# KELU1-0234.net
KiCad netlist of a schematic drawn in EAGLE
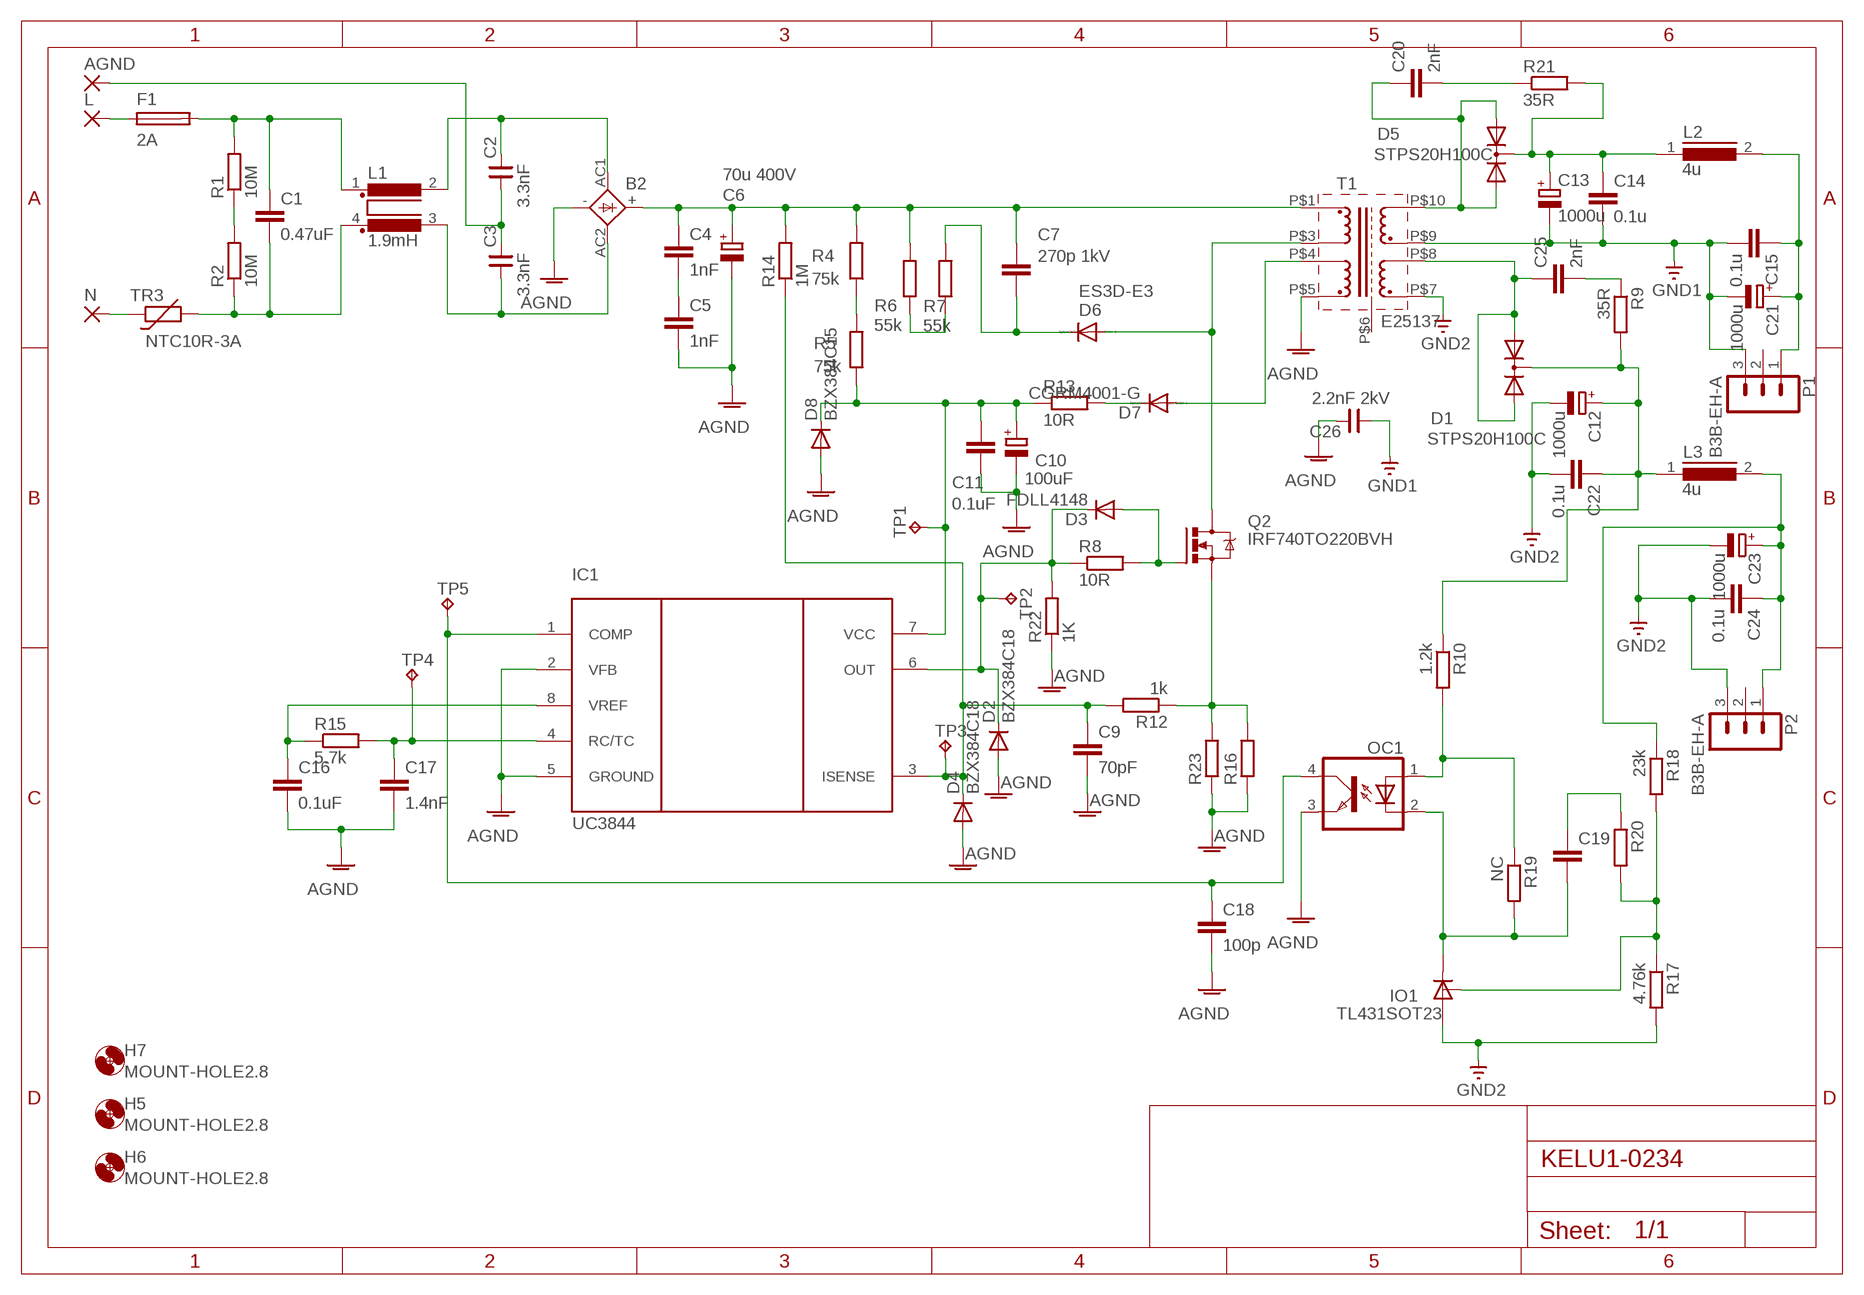
[diagram p0: schematic, sheet 1]

(export (version "E")
  (design (tool "Eeschema 10.0.6"))
  (components
    (comp (ref "AGND")
      (value "3,17/1,1")
      (footprint "eagle-import:3,17_1,1")
      (libsource (lib "eagle-import") (part "3,17/1,1"))
    )
    (comp (ref "B2")
      (value "2KBP")
      (footprint "eagle-import:2KBP")
      (libsource (lib "eagle-import") (part "2KBP"))
    )
    (comp (ref "C1")
      (value "0.47uF")
      (footprint "eagle-import:C15B5")
      (libsource (lib "eagle-import") (part "C15/5"))
    )
    (comp (ref "C2")
      (value "3.3nF")
      (footprint "eagle-import:C085-110X050")
      (libsource (lib "eagle-import") (part "CNP-C085-110X050"))
    )
    (comp (ref "C3")
      (value "3.3nF")
      (footprint "eagle-import:C080-110X045")
      (libsource (lib "eagle-import") (part "CNP-C080-110X045"))
    )
    (comp (ref "C4")
      (value "1nF")
      (footprint "eagle-import:C1206K")
      (libsource (lib "eagle-import") (part "C-EUC1206K"))
    )
    (comp (ref "C5")
      (value "1nF")
      (footprint "eagle-import:C1206K")
      (libsource (lib "eagle-import") (part "C-EUC1206K"))
    )
    (comp (ref "C6")
      (value "70u 400V")
      (footprint "eagle-import:E7,5-16")
      (libsource (lib "eagle-import") (part "CPOL-EUE7.5-16"))
    )
    (comp (ref "C7")
      (value "270p 1kV")
      (footprint "eagle-import:C1206K")
      (libsource (lib "eagle-import") (part "C-EUC1206K"))
    )
    (comp (ref "C9")
      (value "70pF")
      (footprint "eagle-import:C0805K")
      (libsource (lib "eagle-import") (part "resistor_C-EUC0805K"))
    )
    (comp (ref "C10")
      (value "100uF")
      (footprint "eagle-import:E5-5")
      (libsource (lib "eagle-import") (part "resistor_CPOL-EUE5-5"))
    )
    (comp (ref "C11")
      (value "0.1uF")
      (footprint "eagle-import:C0805K")
      (libsource (lib "eagle-import") (part "resistor_C-EUC0805K"))
    )
    (comp (ref "C12")
      (value "1000u")
      (footprint "eagle-import:E3,5-8")
      (libsource (lib "eagle-import") (part "resistor_CPOL-EUE3.5-8"))
    )
    (comp (ref "C13")
      (value "1000u")
      (footprint "eagle-import:E3,5-8")
      (libsource (lib "eagle-import") (part "resistor_CPOL-EUE3.5-8"))
    )
    (comp (ref "C14")
      (value "0.1u")
      (footprint "eagle-import:C0805K")
      (libsource (lib "eagle-import") (part "resistor_C-EUC0805K"))
    )
    (comp (ref "C15")
      (value "0.1u")
      (footprint "eagle-import:C0805K")
      (libsource (lib "eagle-import") (part "resistor_C-EUC0805K"))
    )
    (comp (ref "C16")
      (value "0.1uF")
      (footprint "eagle-import:C0805K")
      (libsource (lib "eagle-import") (part "resistor_C-EUC0805K"))
    )
    (comp (ref "C17")
      (value "1.4nF")
      (footprint "eagle-import:C0805K")
      (libsource (lib "eagle-import") (part "resistor_C-EUC0805K"))
    )
    (comp (ref "C18")
      (value "100p")
      (footprint "eagle-import:C0805K")
      (libsource (lib "eagle-import") (part "resistor_C-EUC0805K"))
    )
    (comp (ref "C19")
      (value "C-EUC0805K")
      (footprint "eagle-import:C0805K")
      (libsource (lib "eagle-import") (part "resistor_C-EUC0805K"))
    )
    (comp (ref "C20")
      (value "2nF")
      (footprint "eagle-import:C1206K")
      (libsource (lib "eagle-import") (part "C-EUC1206K"))
    )
    (comp (ref "C21")
      (value "1000u")
      (footprint "eagle-import:E3,5-8")
      (libsource (lib "eagle-import") (part "resistor_CPOL-EUE3.5-8"))
    )
    (comp (ref "C22")
      (value "0.1u")
      (footprint "eagle-import:C0805K")
      (libsource (lib "eagle-import") (part "resistor_C-EUC0805K"))
    )
    (comp (ref "C23")
      (value "1000u")
      (footprint "eagle-import:E3,5-8")
      (libsource (lib "eagle-import") (part "resistor_CPOL-EUE3.5-8"))
    )
    (comp (ref "C24")
      (value "0.1u")
      (footprint "eagle-import:C0805K")
      (libsource (lib "eagle-import") (part "resistor_C-EUC0805K"))
    )
    (comp (ref "C25")
      (value "2nF")
      (footprint "eagle-import:C1206K")
      (libsource (lib "eagle-import") (part "C-EUC1206K"))
    )
    (comp (ref "C26")
      (value "2.2nF 2kV")
      (footprint "eagle-import:C080-110X045")
      (libsource (lib "eagle-import") (part "CNP-C080-110X045"))
    )
    (comp (ref "D1")
      (value "STPS20H100C")
      (footprint "eagle-import:TO220ABS")
      (libsource (lib "eagle-import") (part "BYV32"))
    )
    (comp (ref "D2")
      (value "BZX384C18")
      (footprint "eagle-import:SOD323-W")
      (libsource (lib "eagle-import") (part "diode-1_DIODE-SOD323-W"))
    )
    (comp (ref "D3")
      (value "FDLL4148")
      (footprint "eagle-import:MINIMELF")
      (libsource (lib "eagle-import") (part "diode-1_DIODE-MINIMELF"))
    )
    (comp (ref "D4")
      (value "BZX384C18")
      (footprint "eagle-import:SOD323-W")
      (libsource (lib "eagle-import") (part "diode-1_DIODE-SOD323-W"))
    )
    (comp (ref "D5")
      (value "STPS20H100C")
      (footprint "eagle-import:TO220ABS")
      (libsource (lib "eagle-import") (part "BYV32"))
    )
    (comp (ref "D6")
      (value "ES3D-E3")
      (footprint "eagle-import:SMC")
      (libsource (lib "eagle-import") (part "DIODE-SMC"))
    )
    (comp (ref "D7")
      (value "CGRM4001-G")
      (footprint "eagle-import:SOD-123_MINI-SMA")
      (libsource (lib "eagle-import") (part "CGRM400-G1"))
    )
    (comp (ref "D8")
      (value "BZX384C15")
      (footprint "eagle-import:SOD323-W")
      (libsource (lib "eagle-import") (part "diode-1_DIODE-SOD323-W"))
    )
    (comp (ref "F1")
      (value "2A")
      (footprint "eagle-import:TE5")
      (libsource (lib "eagle-import") (part "FUSETE5"))
    )
    (comp (ref "H5")
      (value "MOUNT-HOLE2.8")
      (footprint "eagle-import:2,8")
      (libsource (lib "eagle-import") (part "MOUNT-HOLE2.8"))
    )
    (comp (ref "H6")
      (value "MOUNT-HOLE2.8")
      (footprint "eagle-import:2,8")
      (libsource (lib "eagle-import") (part "MOUNT-HOLE2.8"))
    )
    (comp (ref "H7")
      (value "MOUNT-HOLE2.8")
      (footprint "eagle-import:2,8")
      (libsource (lib "eagle-import") (part "MOUNT-HOLE2.8"))
    )
    (comp (ref "IC1")
      (value "UC3844")
      (footprint "eagle-import:SOIC08")
      (libsource (lib "eagle-import") (part "UC3844"))
    )
    (comp (ref "IO1")
      (value "TL431SOT23")
      (footprint "eagle-import:SOT23")
      (fields (field (name "MPN") "TL431BFDT"))
      (libsource (lib "eagle-import") (part "TL431SOT23"))
    )
    (comp (ref "L")
      (value "3,17/1,1")
      (footprint "eagle-import:3,17_1,1")
      (libsource (lib "eagle-import") (part "3,17/1,1"))
    )
    (comp (ref "L1")
      (value "1.9mH")
      (footprint "eagle-import:MFE")
      (libsource (lib "eagle-import") (part "MFE"))
    )
    (comp (ref "L2")
      (value "4u")
      (footprint "eagle-import:82114R")
      (libsource (lib "eagle-import") (part "82114R"))
    )
    (comp (ref "L3")
      (value "4u")
      (footprint "eagle-import:82114R")
      (libsource (lib "eagle-import") (part "82114R"))
    )
    (comp (ref "N")
      (value "3,17/1,1")
      (footprint "eagle-import:3,17_1,1")
      (libsource (lib "eagle-import") (part "3,17/1,1"))
    )
    (comp (ref "OC1")
      (value "PC817")
      (footprint "eagle-import:DIL04")
      (libsource (lib "eagle-import") (part "PC817"))
    )
    (comp (ref "P1")
      (value "B3B-EH-A")
      (footprint "eagle-import:B3B-EH-A")
      (libsource (lib "eagle-import") (part "B3B-EH-A"))
    )
    (comp (ref "P2")
      (value "B3B-EH-A")
      (footprint "eagle-import:B3B-EH-A")
      (libsource (lib "eagle-import") (part "B3B-EH-A"))
    )
    (comp (ref "Q2")
      (value "IRF740TO220BVH")
      (footprint "eagle-import:TO220BVH")
      (libsource (lib "eagle-import") (part "IRF740TO220BVH"))
    )
    (comp (ref "R1")
      (value "10M")
      (footprint "eagle-import:M1206")
      (libsource (lib "eagle-import") (part "R-EU_M1206"))
    )
    (comp (ref "R2")
      (value "10M")
      (footprint "eagle-import:M1206")
      (libsource (lib "eagle-import") (part "R-EU_M1206"))
    )
    (comp (ref "R4")
      (value "75k")
      (footprint "eagle-import:M1206")
      (libsource (lib "eagle-import") (part "R-EU_M1206"))
    )
    (comp (ref "R5")
      (value "75k")
      (footprint "eagle-import:M1206")
      (libsource (lib "eagle-import") (part "R-EU_M1206"))
    )
    (comp (ref "R6")
      (value "55k")
      (footprint "eagle-import:M1206")
      (libsource (lib "eagle-import") (part "R-EU_M1206"))
    )
    (comp (ref "R7")
      (value "55k")
      (footprint "eagle-import:M1206")
      (libsource (lib "eagle-import") (part "R-EU_M1206"))
    )
    (comp (ref "R8")
      (value "10R")
      (footprint "eagle-import:M1206")
      (libsource (lib "eagle-import") (part "resistor_R-EU_M1206"))
    )
    (comp (ref "R9")
      (value "35R")
      (footprint "eagle-import:M1206")
      (libsource (lib "eagle-import") (part "R-EU_M1206"))
    )
    (comp (ref "R10")
      (value "1.2k")
      (footprint "eagle-import:R0805W")
      (libsource (lib "eagle-import") (part "resistor_R-EU_R0805W"))
    )
    (comp (ref "R12")
      (value "1k")
      (footprint "eagle-import:R0805W")
      (libsource (lib "eagle-import") (part "resistor_R-EU_R0805W"))
    )
    (comp (ref "R13")
      (value "10R")
      (footprint "eagle-import:R0805W")
      (libsource (lib "eagle-import") (part "resistor_R-EU_R0805W"))
    )
    (comp (ref "R14")
      (value "1M")
      (footprint "eagle-import:M1206")
      (libsource (lib "eagle-import") (part "R-EU_M1206"))
    )
    (comp (ref "R15")
      (value "5.7k")
      (footprint "eagle-import:R0805W")
      (libsource (lib "eagle-import") (part "resistor_R-EU_R0805W"))
    )
    (comp (ref "R16")
      (value "R-EU_R2512")
      (footprint "eagle-import:R2512")
      (libsource (lib "eagle-import") (part "R-EU_R2512"))
    )
    (comp (ref "R17")
      (value "4.76k")
      (footprint "eagle-import:R0805W")
      (libsource (lib "eagle-import") (part "resistor_R-EU_R0805W"))
    )
    (comp (ref "R18")
      (value "23k")
      (footprint "eagle-import:R0805W")
      (libsource (lib "eagle-import") (part "resistor_R-EU_R0805W"))
    )
    (comp (ref "R19")
      (value "NC")
      (footprint "eagle-import:R0805W")
      (libsource (lib "eagle-import") (part "resistor_R-EU_R0805W"))
    )
    (comp (ref "R20")
      (value "R-EU_R0805W")
      (footprint "eagle-import:R0805W")
      (libsource (lib "eagle-import") (part "resistor_R-EU_R0805W"))
    )
    (comp (ref "R21")
      (value "35R")
      (footprint "eagle-import:M1206")
      (libsource (lib "eagle-import") (part "R-EU_M1206"))
    )
    (comp (ref "R22")
      (value "1K")
      (footprint "eagle-import:M1206")
      (libsource (lib "eagle-import") (part "resistor_R-EU_M1206"))
    )
    (comp (ref "R23")
      (value "R-EU_R2512")
      (footprint "eagle-import:R2512")
      (libsource (lib "eagle-import") (part "R-EU_R2512"))
    )
    (comp (ref "T1")
      (value "E25137")
      (footprint "eagle-import:E25137")
      (libsource (lib "eagle-import") (part "E25137"))
    )
    (comp (ref "TP1")
      (value "TPB1,27")
      (footprint "eagle-import:B1,27")
      (libsource (lib "eagle-import") (part "TPB1,27"))
    )
    (comp (ref "TP2")
      (value "TPB1,27")
      (footprint "eagle-import:B1,27")
      (libsource (lib "eagle-import") (part "TPB1,27"))
    )
    (comp (ref "TP3")
      (value "TPB1,27")
      (footprint "eagle-import:B1,27")
      (libsource (lib "eagle-import") (part "TPB1,27"))
    )
    (comp (ref "TP4")
      (value "TPB1,27")
      (footprint "eagle-import:B1,27")
      (libsource (lib "eagle-import") (part "TPB1,27"))
    )
    (comp (ref "TP5")
      (value "TPB1,27")
      (footprint "eagle-import:B1,27")
      (libsource (lib "eagle-import") (part "TPB1,27"))
    )
    (comp (ref "TR3")
      (value "NTC10R-3A")
      (footprint "eagle-import:R-5")
      (libsource (lib "eagle-import") (part "THERMISTOR-5"))
    )
  )
  (nets
    (net (code "1") (name "AGND") (class "Default")
      (node (ref "B2") (pin "-") (pinfunction "-_-") (pintype "passive"))
      (node (ref "C10") (pin "-") (pinfunction "-_-") (pintype "passive"))
      (node (ref "C11") (pin "2") (pinfunction "2_2") (pintype "passive"))
      (node (ref "C16") (pin "2") (pinfunction "2_2") (pintype "passive"))
      (node (ref "C17") (pin "2") (pinfunction "2_2") (pintype "passive"))
      (node (ref "C18") (pin "2") (pinfunction "2_2") (pintype "passive"))
      (node (ref "C26") (pin "2") (pinfunction "2_2") (pintype "passive"))
      (node (ref "C5") (pin "2") (pinfunction "2_2") (pintype "passive"))
      (node (ref "C6") (pin "-") (pinfunction "-_-") (pintype "passive"))
      (node (ref "C9") (pin "2") (pinfunction "2_2") (pintype "passive"))
      (node (ref "D2") (pin "A") (pinfunction "A_A") (pintype "passive"))
      (node (ref "D4") (pin "A") (pinfunction "A_A") (pintype "passive"))
      (node (ref "D8") (pin "A") (pinfunction "A_A") (pintype "passive"))
      (node (ref "IC1") (pin "2") (pinfunction "VFB_2") (pintype "bidirectional"))
      (node (ref "IC1") (pin "5") (pinfunction "GROUND_5") (pintype "bidirectional"))
      (node (ref "OC1") (pin "3") (pinfunction "EMIT_3") (pintype "passive"))
      (node (ref "R16") (pin "1") (pinfunction "1_1") (pintype "passive"))
      (node (ref "R22") (pin "1") (pinfunction "1_1") (pintype "passive"))
      (node (ref "R23") (pin "1") (pinfunction "1_1") (pintype "passive"))
      (node (ref "T1") (pin "P$5") (pinfunction "5_P$5") (pintype "passive"))
    )
    (net (code "2") (name "GND1") (class "Default")
      (node (ref "C13") (pin "-") (pinfunction "-_-") (pintype "passive"))
      (node (ref "C14") (pin "2") (pinfunction "2_2") (pintype "passive"))
      (node (ref "C15") (pin "2") (pinfunction "2_2") (pintype "passive"))
      (node (ref "C21") (pin "-") (pinfunction "-_-") (pintype "passive"))
      (node (ref "C26") (pin "1") (pinfunction "1_1") (pintype "passive"))
      (node (ref "P1") (pin "3") (pinfunction "3_3") (pintype "passive"))
      (node (ref "T1") (pin "P$9") (pinfunction "9_P$9") (pintype "passive"))
    )
    (net (code "3") (name "GND2") (class "Default")
      (node (ref "C12") (pin "-") (pinfunction "-_-") (pintype "passive"))
      (node (ref "C22") (pin "2") (pinfunction "2_2") (pintype "passive"))
      (node (ref "C23") (pin "-") (pinfunction "-_-") (pintype "passive"))
      (node (ref "C24") (pin "2") (pinfunction "2_2") (pintype "passive"))
      (node (ref "IO1") (pin "3") (pinfunction "A_3") (pintype "bidirectional"))
      (node (ref "P2") (pin "3") (pinfunction "3_3") (pintype "passive"))
      (node (ref "R17") (pin "2") (pinfunction "2_2") (pintype "passive"))
      (node (ref "T1") (pin "P$7") (pinfunction "7_P$7") (pintype "passive"))
    )
    (net (code "4") (name "Net-(AGND-P)") (class "Default")
      (node (ref "AGND") (pin "1") (pinfunction "P_1") (pintype "passive"))
      (node (ref "C2") (pin "1") (pinfunction "1_1") (pintype "passive"))
      (node (ref "C3") (pin "2") (pinfunction "2_2") (pintype "passive"))
    )
    (net (code "5") (name "Net-(B2-PadAC1)") (class "Default")
      (node (ref "B2") (pin "AC1") (pinfunction "AC1_AC1") (pintype "passive"))
      (node (ref "C2") (pin "2") (pinfunction "2_2") (pintype "passive"))
      (node (ref "L1") (pin "2") (pinfunction "2_2") (pintype "passive"))
    )
    (net (code "6") (name "Net-(C1-Pad1)") (class "Default")
      (node (ref "C1") (pin "1") (pinfunction "1_1") (pintype "passive"))
      (node (ref "F1") (pin "2") (pinfunction "2_2") (pintype "passive"))
      (node (ref "L1") (pin "1") (pinfunction "1_1") (pintype "passive"))
      (node (ref "R1") (pin "2") (pinfunction "2_2") (pintype "passive"))
    )
    (net (code "7") (name "Net-(C4-Pad2)") (class "Default")
      (node (ref "C4") (pin "2") (pinfunction "2_2") (pintype "passive"))
      (node (ref "C5") (pin "1") (pinfunction "1_1") (pintype "passive"))
    )
    (net (code "8") (name "Net-(C7-Pad2)") (class "Default")
      (node (ref "C7") (pin "2") (pinfunction "2_2") (pintype "passive"))
      (node (ref "D6") (pin "C") (pinfunction "C_C") (pintype "passive"))
      (node (ref "R7") (pin "2") (pinfunction "2_2") (pintype "passive"))
    )
    (net (code "9") (name "Net-(C12-Pad+)") (class "Default")
      (node (ref "C12") (pin "+") (pinfunction "+_+") (pintype "passive"))
      (node (ref "C22") (pin "1") (pinfunction "1_1") (pintype "passive"))
      (node (ref "D1") (pin "C") (pinfunction "C_C") (pintype "passive"))
      (node (ref "L3") (pin "1") (pinfunction "1_1") (pintype "passive"))
      (node (ref "R10") (pin "1") (pinfunction "1_1") (pintype "passive"))
      (node (ref "R9") (pin "2") (pinfunction "2_2") (pintype "passive"))
    )
    (net (code "10") (name "Net-(C13-Pad+)") (class "Default")
      (node (ref "C13") (pin "+") (pinfunction "+_+") (pintype "passive"))
      (node (ref "C14") (pin "1") (pinfunction "1_1") (pintype "passive"))
      (node (ref "D5") (pin "C") (pinfunction "C_C") (pintype "passive"))
      (node (ref "L2") (pin "1") (pinfunction "1_1") (pintype "passive"))
      (node (ref "R21") (pin "2") (pinfunction "2_2") (pintype "passive"))
    )
    (net (code "11") (name "Net-(C15-Pad1)") (class "Default")
      (node (ref "C15") (pin "1") (pinfunction "1_1") (pintype "passive"))
      (node (ref "C21") (pin "+") (pinfunction "+_+") (pintype "passive"))
      (node (ref "L2") (pin "2") (pinfunction "2_2") (pintype "passive"))
      (node (ref "P1") (pin "1") (pinfunction "1_1") (pintype "passive"))
    )
    (net (code "12") (name "Net-(C19-Pad1)") (class "Default")
      (node (ref "C19") (pin "1") (pinfunction "1_1") (pintype "passive"))
      (node (ref "R20") (pin "1") (pinfunction "1_1") (pintype "passive"))
    )
    (net (code "13") (name "Net-(C20-Pad2)") (class "Default")
      (node (ref "C20") (pin "2") (pinfunction "2_2") (pintype "passive"))
      (node (ref "R21") (pin "1") (pinfunction "1_1") (pintype "passive"))
    )
    (net (code "14") (name "Net-(C23-Pad+)") (class "Default")
      (node (ref "C23") (pin "+") (pinfunction "+_+") (pintype "passive"))
      (node (ref "C24") (pin "1") (pinfunction "1_1") (pintype "passive"))
      (node (ref "L3") (pin "2") (pinfunction "2_2") (pintype "passive"))
      (node (ref "P2") (pin "1") (pinfunction "1_1") (pintype "passive"))
      (node (ref "R18") (pin "1") (pinfunction "1_1") (pintype "passive"))
    )
    (net (code "15") (name "Net-(C25-Pad2)") (class "Default")
      (node (ref "C25") (pin "2") (pinfunction "2_2") (pintype "passive"))
      (node (ref "R9") (pin "1") (pinfunction "1_1") (pintype "passive"))
    )
    (net (code "16") (name "Net-(D3-PadA)") (class "Default")
      (node (ref "D3") (pin "A") (pinfunction "A_A") (pintype "passive"))
      (node (ref "Q2") (pin "G") (pinfunction "G_G") (pintype "passive"))
      (node (ref "R8") (pin "2") (pinfunction "2_2") (pintype "passive"))
    )
    (net (code "17") (name "Net-(D7-PadC)") (class "Default")
      (node (ref "D7") (pin "C") (pinfunction "C_C") (pintype "passive"))
      (node (ref "R13") (pin "2") (pinfunction "2_2") (pintype "passive"))
    )
    (net (code "18") (name "Net-(IC1-COMP)") (class "Default")
      (node (ref "C18") (pin "1") (pinfunction "1_1") (pintype "passive"))
      (node (ref "IC1") (pin "1") (pinfunction "COMP_1") (pintype "bidirectional"))
      (node (ref "OC1") (pin "4") (pinfunction "COL_4") (pintype "passive"))
      (node (ref "TP5") (pin "PP") (pinfunction "TP_PP") (pintype "input"))
    )
    (net (code "19") (name "Net-(IC1-ISENSE)") (class "Default")
      (node (ref "C9") (pin "1") (pinfunction "1_1") (pintype "passive"))
      (node (ref "D4") (pin "C") (pinfunction "C_C") (pintype "passive"))
      (node (ref "IC1") (pin "3") (pinfunction "ISENSE_3") (pintype "bidirectional"))
      (node (ref "R12") (pin "2") (pinfunction "2_2") (pintype "passive"))
      (node (ref "R14") (pin "1") (pinfunction "1_1") (pintype "passive"))
      (node (ref "TP3") (pin "PP") (pinfunction "TP_PP") (pintype "input"))
    )
    (net (code "20") (name "Net-(IC1-OUT)") (class "Default")
      (node (ref "D2") (pin "C") (pinfunction "C_C") (pintype "passive"))
      (node (ref "D3") (pin "C") (pinfunction "C_C") (pintype "passive"))
      (node (ref "IC1") (pin "6") (pinfunction "OUT_6") (pintype "bidirectional"))
      (node (ref "R22") (pin "2") (pinfunction "2_2") (pintype "passive"))
      (node (ref "R8") (pin "1") (pinfunction "1_1") (pintype "passive"))
      (node (ref "TP2") (pin "PP") (pinfunction "TP_PP") (pintype "input"))
    )
    (net (code "21") (name "Net-(IC1-RC{slash}TC)") (class "Default")
      (node (ref "C17") (pin "1") (pinfunction "1_1") (pintype "passive"))
      (node (ref "IC1") (pin "4") (pinfunction "RC/TC_4") (pintype "bidirectional"))
      (node (ref "R15") (pin "2") (pinfunction "2_2") (pintype "passive"))
      (node (ref "TP4") (pin "PP") (pinfunction "TP_PP") (pintype "input"))
    )
    (net (code "22") (name "Net-(IC1-VCC)") (class "Default")
      (node (ref "C10") (pin "+") (pinfunction "+_+") (pintype "passive"))
      (node (ref "C11") (pin "1") (pinfunction "1_1") (pintype "passive"))
      (node (ref "D8") (pin "C") (pinfunction "C_C") (pintype "passive"))
      (node (ref "IC1") (pin "7") (pinfunction "VCC_7") (pintype "bidirectional"))
      (node (ref "R13") (pin "1") (pinfunction "1_1") (pintype "passive"))
      (node (ref "R5") (pin "1") (pinfunction "1_1") (pintype "passive"))
      (node (ref "TP1") (pin "PP") (pinfunction "TP_PP") (pintype "input"))
    )
    (net (code "23") (name "Net-(IC1-VREF)") (class "Default")
      (node (ref "C16") (pin "1") (pinfunction "1_1") (pintype "passive"))
      (node (ref "IC1") (pin "8") (pinfunction "VREF_8") (pintype "bidirectional"))
      (node (ref "R15") (pin "1") (pinfunction "1_1") (pintype "passive"))
    )
    (net (code "24") (name "Net-(IO1-C)") (class "Default")
      (node (ref "C19") (pin "2") (pinfunction "2_2") (pintype "passive"))
      (node (ref "IO1") (pin "1") (pinfunction "C_1") (pintype "bidirectional"))
      (node (ref "OC1") (pin "2") (pinfunction "C_2") (pintype "passive"))
      (node (ref "R19") (pin "2") (pinfunction "2_2") (pintype "passive"))
    )
    (net (code "25") (name "Net-(IO1-R)") (class "Default")
      (node (ref "IO1") (pin "2") (pinfunction "R_2") (pintype "bidirectional"))
      (node (ref "R17") (pin "1") (pinfunction "1_1") (pintype "passive"))
      (node (ref "R18") (pin "2") (pinfunction "2_2") (pintype "passive"))
      (node (ref "R20") (pin "2") (pinfunction "2_2") (pintype "passive"))
    )
    (net (code "26") (name "Net-(L-P)") (class "Default")
      (node (ref "F1") (pin "1") (pinfunction "1_1") (pintype "passive"))
      (node (ref "L") (pin "1") (pinfunction "P_1") (pintype "passive"))
    )
    (net (code "27") (name "Net-(L1-3)") (class "Default")
      (node (ref "C1") (pin "2") (pinfunction "2_2") (pintype "passive"))
      (node (ref "L1") (pin "4") (pinfunction "3_4") (pintype "passive"))
      (node (ref "R2") (pin "1") (pinfunction "1_1") (pintype "passive"))
      (node (ref "TR3") (pin "2") (pinfunction "2_2") (pintype "passive"))
    )
    (net (code "28") (name "Net-(L1-4)") (class "Default")
      (node (ref "B2") (pin "AC2") (pinfunction "AC2_AC2") (pintype "passive"))
      (node (ref "C3") (pin "1") (pinfunction "1_1") (pintype "passive"))
      (node (ref "L1") (pin "3") (pinfunction "4_3") (pintype "passive"))
    )
    (net (code "29") (name "Net-(N-P)") (class "Default")
      (node (ref "N") (pin "1") (pinfunction "P_1") (pintype "passive"))
      (node (ref "TR3") (pin "1") (pinfunction "1_1") (pintype "passive"))
    )
    (net (code "30") (name "Net-(OC1-A)") (class "Default")
      (node (ref "OC1") (pin "1") (pinfunction "A_1") (pintype "passive"))
      (node (ref "R10") (pin "2") (pinfunction "2_2") (pintype "passive"))
      (node (ref "R19") (pin "1") (pinfunction "1_1") (pintype "passive"))
    )
    (net (code "31") (name "Net-(Q2-PadS)") (class "Default")
      (node (ref "Q2") (pin "S") (pinfunction "S_S") (pintype "passive"))
      (node (ref "R12") (pin "1") (pinfunction "1_1") (pintype "passive"))
      (node (ref "R16") (pin "2") (pinfunction "2_2") (pintype "passive"))
      (node (ref "R23") (pin "2") (pinfunction "2_2") (pintype "passive"))
    )
    (net (code "32") (name "Net-(R1-Pad1)") (class "Default")
      (node (ref "R1") (pin "1") (pinfunction "1_1") (pintype "passive"))
      (node (ref "R2") (pin "2") (pinfunction "2_2") (pintype "passive"))
    )
    (net (code "33") (name "Net-(R4-Pad1)") (class "Default")
      (node (ref "R4") (pin "1") (pinfunction "1_1") (pintype "passive"))
      (node (ref "R5") (pin "2") (pinfunction "2_2") (pintype "passive"))
    )
    (net (code "34") (name "Net-(R6-Pad1)") (class "Default")
      (node (ref "R6") (pin "1") (pinfunction "1_1") (pintype "passive"))
      (node (ref "R7") (pin "1") (pinfunction "1_1") (pintype "passive"))
    )
    (net (code "35") (name "Net-(T1-1)") (class "Default")
      (node (ref "B2") (pin "+") (pinfunction "+_+") (pintype "passive"))
      (node (ref "C4") (pin "1") (pinfunction "1_1") (pintype "passive"))
      (node (ref "C6") (pin "+") (pinfunction "+_+") (pintype "passive"))
      (node (ref "C7") (pin "1") (pinfunction "1_1") (pintype "passive"))
      (node (ref "R14") (pin "2") (pinfunction "2_2") (pintype "passive"))
      (node (ref "R4") (pin "2") (pinfunction "2_2") (pintype "passive"))
      (node (ref "R6") (pin "2") (pinfunction "2_2") (pintype "passive"))
      (node (ref "T1") (pin "P$1") (pinfunction "1_P$1") (pintype "passive"))
    )
    (net (code "36") (name "Net-(T1-3)") (class "Default")
      (node (ref "D6") (pin "A") (pinfunction "A_A") (pintype "passive"))
      (node (ref "Q2") (pin "D") (pinfunction "D_D") (pintype "passive"))
      (node (ref "T1") (pin "P$3") (pinfunction "3_P$3") (pintype "passive"))
    )
    (net (code "37") (name "Net-(T1-4)") (class "Default")
      (node (ref "D7") (pin "A") (pinfunction "A_A") (pintype "passive"))
      (node (ref "T1") (pin "P$4") (pinfunction "4_P$4") (pintype "passive"))
    )
    (net (code "38") (name "Net-(T1-8)") (class "Default")
      (node (ref "C25") (pin "1") (pinfunction "1_1") (pintype "passive"))
      (node (ref "D1") (pin "A1") (pinfunction "A1_A1") (pintype "passive"))
      (node (ref "D1") (pin "A2") (pinfunction "A2_A2") (pintype "passive"))
      (node (ref "T1") (pin "P$8") (pinfunction "8_P$8") (pintype "passive"))
    )
    (net (code "39") (name "Net-(T1-10)") (class "Default")
      (node (ref "C20") (pin "1") (pinfunction "1_1") (pintype "passive"))
      (node (ref "D5") (pin "A1") (pinfunction "A1_A1") (pintype "passive"))
      (node (ref "D5") (pin "A2") (pinfunction "A2_A2") (pintype "passive"))
      (node (ref "T1") (pin "P$10") (pinfunction "10_P$10") (pintype "passive"))
    )
    (net (code "40") (name "unconnected-(P1-Pad2)") (class "Default")
      (node (ref "P1") (pin "2") (pinfunction "2_2") (pintype "passive"))
    )
    (net (code "41") (name "unconnected-(P2-Pad2)") (class "Default")
      (node (ref "P2") (pin "2") (pinfunction "2_2") (pintype "passive"))
    )
    (net (code "42") (name "unconnected-(T1-6-PadP$6)") (class "Default")
      (node (ref "T1") (pin "P$6") (pinfunction "6_P$6") (pintype "passive"))
    )
  )
)
